# main.net
KiCad netlist of a schematic drawn in EAGLE
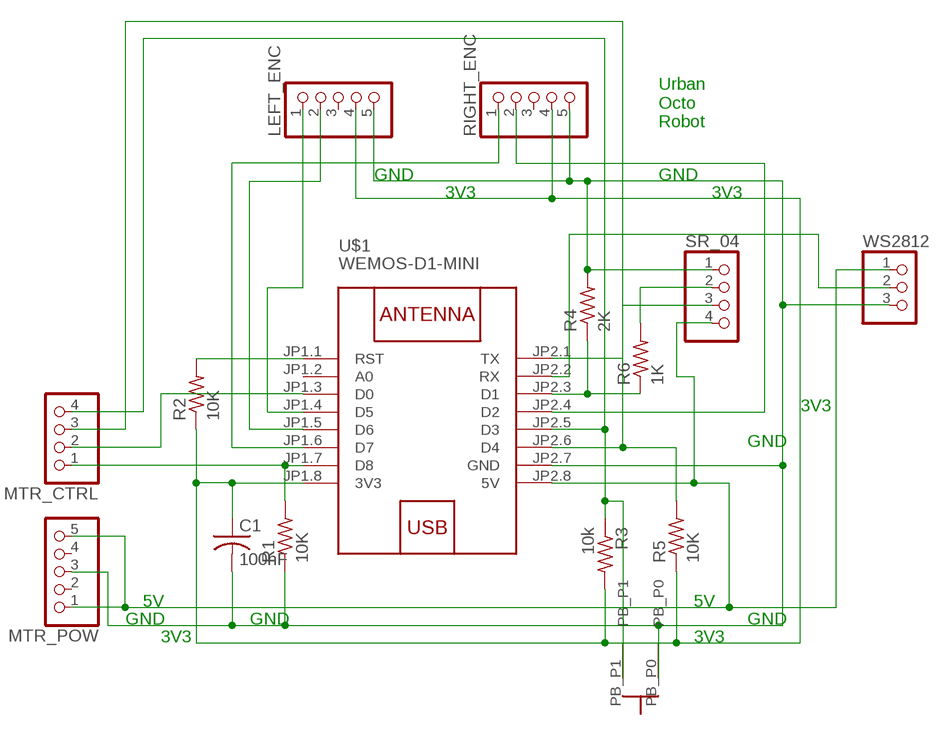
[diagram p0: schematic, sheet 1]

(export (version "E")
  (design (tool "Eeschema 10.0.6"))
  (components
    (comp (ref "C1")
      (value "100nF")
      (footprint "eagle-import:C050-024X044")
      (libsource (lib "eagle-import") (part "C-US050-024X044"))
    )
    (comp (ref "LEFT_ENC")
      (value "PINHD-1X5")
      (footprint "eagle-import:1X05")
      (libsource (lib "eagle-import") (part "PINHD-1X5"))
    )
    (comp (ref "MTR_CTRL")
      (value "PINHD-1X4")
      (footprint "eagle-import:1X04")
      (libsource (lib "eagle-import") (part "PINHD-1X4"))
    )
    (comp (ref "MTR_POW")
      (value "PINHD-1X5/90")
      (footprint "eagle-import:1X05_90")
      (libsource (lib "eagle-import") (part "PINHD-1X5/90"))
    )
    (comp (ref "R1")
      (value "10K")
      (footprint "eagle-import:0204_7")
      (libsource (lib "eagle-import") (part "R-US_0204/7"))
    )
    (comp (ref "R2")
      (value "10K")
      (footprint "eagle-import:0204_7")
      (libsource (lib "eagle-import") (part "R-US_0204/7"))
    )
    (comp (ref "R3")
      (value "10k")
      (footprint "eagle-import:0207_2V")
      (libsource (lib "eagle-import") (part "R-US_0207/2V"))
    )
    (comp (ref "R4")
      (value "2K")
      (footprint "eagle-import:0309V")
      (libsource (lib "eagle-import") (part "R-US_0309/V"))
    )
    (comp (ref "R5")
      (value "10K")
      (footprint "eagle-import:0204_7")
      (libsource (lib "eagle-import") (part "R-US_0204/7"))
    )
    (comp (ref "R6")
      (value "1K")
      (footprint "eagle-import:0309V")
      (libsource (lib "eagle-import") (part "R-US_0309/V"))
    )
    (comp (ref "RIGHT_ENC")
      (value "PINHD-1X5")
      (footprint "eagle-import:1X05")
      (libsource (lib "eagle-import") (part "PINHD-1X5"))
    )
    (comp (ref "SR_04")
      (value "PINHD-1X4")
      (footprint "eagle-import:1X04")
      (libsource (lib "eagle-import") (part "PINHD-1X4"))
    )
    (comp (ref "U$1")
      (value "WEMOS-D1-MINI")
      (footprint "eagle-import:WEMOS-D1-MINI")
      (libsource (lib "eagle-import") (part "WEMOS-D1-MINI"))
    )
    (comp (ref "U$7")
      (value "BUTTON6X6X10MMSIDE")
      (footprint "eagle-import:BUTTON6X6X10MMSIDE")
      (libsource (lib "eagle-import") (part "BUTTON6X6X10MMSIDE"))
    )
    (comp (ref "WS2812")
      (value "PINHD-1X3")
      (footprint "eagle-import:1X03")
      (libsource (lib "eagle-import") (part "PINHD-1X3"))
    )
  )
  (nets
    (net (code "1") (name "Net-(R6-Pad2)") (class "Default")
      (node (ref "R6") (pin "2") (pinfunction "2_2") (pintype "passive"))
      (node (ref "SR_04") (pin "2") (pinfunction "2_2") (pintype "passive"))
    )
    (net (code "2") (name "Net-(U$1-3V3)") (class "Default")
      (node (ref "C1") (pin "1") (pinfunction "1_1") (pintype "passive"))
      (node (ref "LEFT_ENC") (pin "4") (pinfunction "4_4") (pintype "passive"))
      (node (ref "R2") (pin "1") (pinfunction "1_1") (pintype "passive"))
      (node (ref "R3") (pin "2") (pinfunction "2_2") (pintype "passive"))
      (node (ref "R5") (pin "1") (pinfunction "1_1") (pintype "passive"))
      (node (ref "RIGHT_ENC") (pin "4") (pinfunction "4_4") (pintype "passive"))
      (node (ref "U$1") (pin "JP1.8") (pinfunction "3V3_JP1.8") (pintype "power_in"))
    )
    (net (code "3") (name "Net-(U$1-5V)") (class "Default")
      (node (ref "MTR_POW") (pin "1") (pinfunction "1_1") (pintype "passive"))
      (node (ref "MTR_POW") (pin "5") (pinfunction "5_5") (pintype "passive"))
      (node (ref "SR_04") (pin "4") (pinfunction "4_4") (pintype "passive"))
      (node (ref "U$1") (pin "JP2.8") (pinfunction "5V_JP2.8") (pintype "power_in"))
      (node (ref "WS2812") (pin "1") (pinfunction "1_1") (pintype "passive"))
    )
    (net (code "4") (name "Net-(U$1-D0)") (class "Default")
      (node (ref "MTR_CTRL") (pin "2") (pinfunction "2_2") (pintype "passive"))
      (node (ref "U$1") (pin "JP1.3") (pinfunction "D0_JP1.3") (pintype "bidirectional"))
    )
    (net (code "5") (name "Net-(U$1-D1)") (class "Default")
      (node (ref "R4") (pin "1") (pinfunction "1_1") (pintype "passive"))
      (node (ref "R6") (pin "1") (pinfunction "1_1") (pintype "passive"))
      (node (ref "U$1") (pin "JP2.3") (pinfunction "D1_JP2.3") (pintype "bidirectional"))
    )
    (net (code "6") (name "Net-(U$1-D2)") (class "Default")
      (node (ref "RIGHT_ENC") (pin "2") (pinfunction "2_2") (pintype "passive"))
      (node (ref "U$1") (pin "JP2.4") (pinfunction "D2_JP2.4") (pintype "bidirectional"))
    )
    (net (code "7") (name "Net-(U$1-D3)") (class "Default")
      (node (ref "MTR_CTRL") (pin "4") (pinfunction "4_4") (pintype "passive"))
      (node (ref "R3") (pin "1") (pinfunction "1_1") (pintype "passive"))
      (node (ref "U$1") (pin "JP2.5") (pinfunction "D3_JP2.5") (pintype "bidirectional"))
      (node (ref "U$7") (pin "PB_P1") (pinfunction "PB_P1_PB_P1") (pintype "bidirectional"))
    )
    (net (code "8") (name "Net-(U$1-D4)") (class "Default")
      (node (ref "MTR_CTRL") (pin "3") (pinfunction "3_3") (pintype "passive"))
      (node (ref "R5") (pin "2") (pinfunction "2_2") (pintype "passive"))
      (node (ref "U$1") (pin "JP2.6") (pinfunction "D4_JP2.6") (pintype "bidirectional"))
    )
    (net (code "9") (name "Net-(U$1-D5)") (class "Default")
      (node (ref "LEFT_ENC") (pin "1") (pinfunction "1_1") (pintype "passive"))
      (node (ref "U$1") (pin "JP1.4") (pinfunction "D5_JP1.4") (pintype "bidirectional"))
    )
    (net (code "10") (name "Net-(U$1-D6)") (class "Default")
      (node (ref "LEFT_ENC") (pin "2") (pinfunction "2_2") (pintype "passive"))
      (node (ref "U$1") (pin "JP1.5") (pinfunction "D6_JP1.5") (pintype "bidirectional"))
    )
    (net (code "11") (name "Net-(U$1-D7)") (class "Default")
      (node (ref "RIGHT_ENC") (pin "1") (pinfunction "1_1") (pintype "passive"))
      (node (ref "U$1") (pin "JP1.6") (pinfunction "D7_JP1.6") (pintype "bidirectional"))
    )
    (net (code "12") (name "Net-(U$1-D8)") (class "Default")
      (node (ref "MTR_CTRL") (pin "1") (pinfunction "1_1") (pintype "passive"))
      (node (ref "R1") (pin "2") (pinfunction "2_2") (pintype "passive"))
      (node (ref "U$1") (pin "JP1.7") (pinfunction "D8_JP1.7") (pintype "bidirectional"))
    )
    (net (code "13") (name "Net-(U$1-GND)") (class "Default")
      (node (ref "C1") (pin "2") (pinfunction "2_2") (pintype "passive"))
      (node (ref "LEFT_ENC") (pin "5") (pinfunction "5_5") (pintype "passive"))
      (node (ref "MTR_POW") (pin "3") (pinfunction "3_3") (pintype "passive"))
      (node (ref "R1") (pin "1") (pinfunction "1_1") (pintype "passive"))
      (node (ref "R4") (pin "2") (pinfunction "2_2") (pintype "passive"))
      (node (ref "RIGHT_ENC") (pin "5") (pinfunction "5_5") (pintype "passive"))
      (node (ref "SR_04") (pin "1") (pinfunction "1_1") (pintype "passive"))
      (node (ref "U$1") (pin "JP2.7") (pinfunction "GND_JP2.7") (pintype "power_in"))
      (node (ref "U$7") (pin "PB_P0") (pinfunction "PB_P0_PB_P0") (pintype "bidirectional"))
      (node (ref "WS2812") (pin "3") (pinfunction "3_3") (pintype "passive"))
    )
    (net (code "14") (name "Net-(U$1-RST)") (class "Default")
      (node (ref "R2") (pin "2") (pinfunction "2_2") (pintype "passive"))
      (node (ref "U$1") (pin "JP1.1") (pinfunction "RST_JP1.1") (pintype "bidirectional"))
    )
    (net (code "15") (name "Net-(U$1-RX)") (class "Default")
      (node (ref "U$1") (pin "JP2.2") (pinfunction "RX_JP2.2") (pintype "bidirectional"))
      (node (ref "WS2812") (pin "2") (pinfunction "2_2") (pintype "passive"))
    )
    (net (code "16") (name "Net-(U$1-TX)") (class "Default")
      (node (ref "SR_04") (pin "3") (pinfunction "3_3") (pintype "passive"))
      (node (ref "U$1") (pin "JP2.1") (pinfunction "TX_JP2.1") (pintype "bidirectional"))
    )
    (net (code "17") (name "unconnected-(LEFT_ENC-Pad3)") (class "Default")
      (node (ref "LEFT_ENC") (pin "3") (pinfunction "3_3") (pintype "passive"))
    )
    (net (code "18") (name "unconnected-(MTR_POW-Pad2)") (class "Default")
      (node (ref "MTR_POW") (pin "2") (pinfunction "2_2") (pintype "passive"))
    )
    (net (code "19") (name "unconnected-(MTR_POW-Pad4)") (class "Default")
      (node (ref "MTR_POW") (pin "4") (pinfunction "4_4") (pintype "passive"))
    )
    (net (code "20") (name "unconnected-(RIGHT_ENC-Pad3)") (class "Default")
      (node (ref "RIGHT_ENC") (pin "3") (pinfunction "3_3") (pintype "passive"))
    )
    (net (code "21") (name "unconnected-(U$1-A0-PadJP1.2)") (class "Default")
      (node (ref "U$1") (pin "JP1.2") (pinfunction "A0_JP1.2") (pintype "bidirectional"))
    )
  )
)
